# BREAKOUT_GUVC.net
KiCad netlist of a schematic drawn in EAGLE
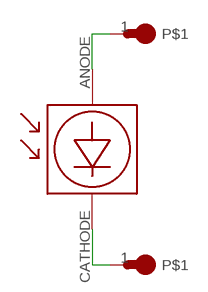
[diagram p0: schematic, sheet 1]

(export (version "E")
  (design (tool "Eeschema 10.0.6"))
  (components
    (comp (ref "1")
      (value "JP0")
      (footprint "eagle-import:JP0")
      (libsource (lib "eagle-import") (part "JP0"))
    )
    (comp (ref "2")
      (value "JP0")
      (footprint "eagle-import:JP0")
      (libsource (lib "eagle-import") (part "JP0"))
    )
    (comp (ref "U$1")
      (value "GUVC-S10GD")
      (footprint "eagle-import:GUVD-S10GD")
      (libsource (lib "eagle-import") (part "GUVC-S10GD"))
    )
  )
  (nets
    (net (code "1") (name "Net-(1-P$1)") (class "Default")
      (node (ref "1") (pin "1") (pinfunction "P$1_1") (pintype "bidirectional"))
      (node (ref "U$1") (pin "ANODE") (pinfunction "ANODE_ANODE") (pintype "bidirectional"))
    )
    (net (code "2") (name "Net-(2-P$1)") (class "Default")
      (node (ref "2") (pin "1") (pinfunction "P$1_1") (pintype "bidirectional"))
      (node (ref "U$1") (pin "CATHODE") (pinfunction "CATHODE_CATHODE") (pintype "bidirectional"))
    )
  )
)
